# design.net
KiCad netlist of a schematic drawn in Altium Designer
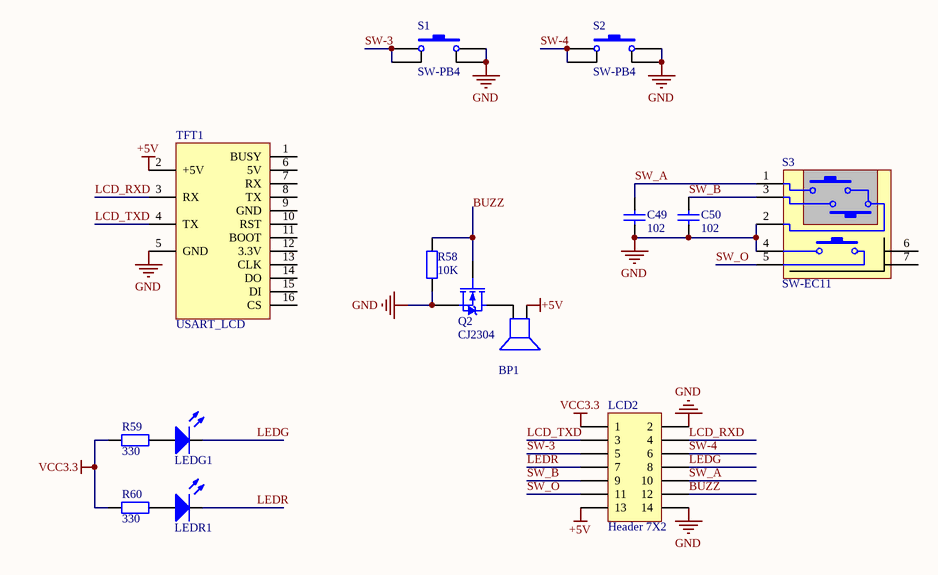
[diagram p0: 显示面板.SchDoc]

(export (version "E")
  (design (tool "Eeschema 10.0.6"))
  (components
    (comp (ref "BP1")
      (value "BUZZER")
      (footprint "蜂鸣器")
      (description "蜂鸣器")
      (libsource (lib "MY_Library") (part "BUZZER"))
    )
    (comp (ref "C49")
      (value "102")
      (footprint "C-RAD-0603")
      (description "无极性电容")
      (fields (field (name "Comment") "Cap") (field (name "PUBLISHER") "Altium Limited"))
      (libsource (lib "Fszhang") (part "Cap"))
    )
    (comp (ref "C50")
      (value "102")
      (footprint "C-RAD-0603")
      (description "无极性电容")
      (fields (field (name "Comment") "Cap") (field (name "PUBLISHER") "Altium Limited"))
      (libsource (lib "Fszhang") (part "Cap"))
    )
    (comp (ref "LCD2")
      (value "Header 7X2")
      (footprint "HDR7X2_A1")
      (description "Header, 7-Pin")
      (fields (field (name "PUBLISHER") "Altium Limited"))
      (libsource (lib "Fszhang") (part "Header 7X2"))
    )
    (comp (ref "LEDG1") (value "COLOUR") (footprint "LEDφ6") (libsource (lib "MY_Library") (part "ledφ6")))
    (comp (ref "LEDR1") (value "COLOUR") (footprint "LEDφ6") (libsource (lib "MY_Library") (part "ledφ6")))
    (comp (ref "Q2")
      (value "CJ2304")
      (footprint "SOT-23")
      (description "N-Channel MOSFET")
      (fields (field (name "PUBLISHER") "Altium Limited"))
      (libsource (lib "Fszhang") (part "MOSFET-N"))
    )
    (comp (ref "R58")
      (value "10K")
      (footprint "0603-1")
      (description "贴片电阻")
      (fields (field (name "Comment") "Res1") (field (name "PUBLISHER") "Altium Limited"))
      (libsource (lib "") (part "Res1_1"))
    )
    (comp (ref "R59")
      (value "330")
      (footprint "0603-1")
      (description "贴片电阻")
      (fields (field (name "Comment") "Res1") (field (name "PUBLISHER") "Altium Limited"))
      (libsource (lib "Fszhang") (part "Res1"))
    )
    (comp (ref "R60")
      (value "330")
      (footprint "0603-1")
      (description "贴片电阻")
      (fields (field (name "Comment") "Res1") (field (name "PUBLISHER") "Altium Limited"))
      (libsource (lib "Fszhang") (part "Res1"))
    )
    (comp (ref "S1")
      (value "SW-PB4")
      (footprint "SW_PB4_A1")
      (description "微动开关")
      (fields (field (name "PUBLISHER") "Altium Limited"))
      (libsource (lib "Fszhang") (part "SW-PB4"))
    )
    (comp (ref "S2")
      (value "SW-PB4")
      (footprint "SW_PB4_A1")
      (description "微动开关")
      (fields (field (name "PUBLISHER") "Altium Limited"))
      (libsource (lib "Fszhang") (part "SW-PB4"))
    )
    (comp (ref "S3")
      (value "SW-EC11")
      (footprint "EC11")
      (description "旋转编码开关")
      (fields (field (name "PUBLISHER") "Altium Limited"))
      (libsource (lib "Fszhang") (part "SW-EC11"))
    )
    (comp (ref "TFT1")
      (value "USART_LCD")
      (footprint "3.5寸")
      (description "usart串口屏")
      (libsource (lib "UASRT_LCD") (part "USART_LCD"))
    )
  )
  (nets
    (net (code "1") (name "+5V") (class "Default")
      (node (ref "BP1") (pin "1") (pinfunction "+_1") (pintype "passive"))
      (node (ref "LCD2") (pin "13") (pinfunction "13_13") (pintype "passive"))
      (node (ref "TFT1") (pin "2") (pinfunction "+5V_2") (pintype "passive"))
    )
    (net (code "2") (name "/BUZZ") (class "Default")
      (node (ref "LCD2") (pin "12") (pinfunction "12_12") (pintype "passive"))
      (node (ref "Q2") (pin "1") (pinfunction "G_1") (pintype "passive"))
      (node (ref "R58") (pin "2") (pinfunction "2_2") (pintype "passive"))
    )
    (net (code "3") (name "/LCD_RXD") (class "Default")
      (node (ref "LCD2") (pin "4") (pinfunction "4_4") (pintype "passive"))
      (node (ref "TFT1") (pin "3") (pinfunction "RX_3") (pintype "passive"))
    )
    (net (code "4") (name "/LCD_TXD") (class "Default")
      (node (ref "LCD2") (pin "3") (pinfunction "3_3") (pintype "passive"))
      (node (ref "TFT1") (pin "4") (pinfunction "TX_4") (pintype "passive"))
    )
    (net (code "5") (name "/LEDG") (class "Default")
      (node (ref "LCD2") (pin "8") (pinfunction "8_8") (pintype "passive"))
      (node (ref "LEDG1") (pin "2") (pinfunction "-_2") (pintype "passive"))
    )
    (net (code "6") (name "/LEDR") (class "Default")
      (node (ref "LCD2") (pin "7") (pinfunction "7_7") (pintype "passive"))
      (node (ref "LEDR1") (pin "2") (pinfunction "-_2") (pintype "passive"))
    )
    (net (code "7") (name "/SW-3") (class "Default")
      (node (ref "LCD2") (pin "5") (pinfunction "5_5") (pintype "passive"))
      (node (ref "S1") (pin "1") (pinfunction "1_1") (pintype "passive"))
      (node (ref "S1") (pin "4") (pinfunction "4_4") (pintype "passive"))
    )
    (net (code "8") (name "/SW-4") (class "Default")
      (node (ref "LCD2") (pin "6") (pinfunction "6_6") (pintype "passive"))
      (node (ref "S2") (pin "1") (pinfunction "1_1") (pintype "passive"))
      (node (ref "S2") (pin "4") (pinfunction "4_4") (pintype "passive"))
    )
    (net (code "9") (name "/SW_A") (class "Default")
      (node (ref "C49") (pin "2") (pinfunction "2_2") (pintype "passive"))
      (node (ref "LCD2") (pin "10") (pinfunction "10_10") (pintype "passive"))
      (node (ref "S3") (pin "1") (pinfunction "1_1") (pintype "passive"))
    )
    (net (code "10") (name "/SW_B") (class "Default")
      (node (ref "C50") (pin "2") (pinfunction "2_2") (pintype "passive"))
      (node (ref "LCD2") (pin "9") (pinfunction "9_9") (pintype "passive"))
      (node (ref "S3") (pin "3") (pinfunction "3_3") (pintype "passive"))
    )
    (net (code "11") (name "/SW_O") (class "Default")
      (node (ref "LCD2") (pin "11") (pinfunction "11_11") (pintype "passive"))
      (node (ref "S3") (pin "5") (pinfunction "5_5") (pintype "passive"))
    )
    (net (code "12") (name "GND") (class "Default")
      (node (ref "C49") (pin "1") (pinfunction "1_1") (pintype "passive"))
      (node (ref "C50") (pin "1") (pinfunction "1_1") (pintype "passive"))
      (node (ref "LCD2") (pin "14") (pinfunction "14_14") (pintype "passive"))
      (node (ref "LCD2") (pin "2") (pinfunction "2_2") (pintype "passive"))
      (node (ref "Q2") (pin "2") (pinfunction "S_2") (pintype "passive"))
      (node (ref "R58") (pin "1") (pinfunction "1_1") (pintype "passive"))
      (node (ref "S1") (pin "2") (pinfunction "2_2") (pintype "passive"))
      (node (ref "S1") (pin "3") (pinfunction "3_3") (pintype "passive"))
      (node (ref "S2") (pin "2") (pinfunction "2_2") (pintype "passive"))
      (node (ref "S2") (pin "3") (pinfunction "3_3") (pintype "passive"))
      (node (ref "S3") (pin "2") (pinfunction "2_2") (pintype "passive"))
      (node (ref "S3") (pin "4") (pinfunction "4_4") (pintype "passive"))
      (node (ref "TFT1") (pin "5") (pinfunction "GND_5") (pintype "passive"))
    )
    (net (code "13") (name "Net-(BP1--)") (class "Default")
      (node (ref "BP1") (pin "2") (pinfunction "-_2") (pintype "passive"))
      (node (ref "Q2") (pin "3") (pinfunction "D_3") (pintype "passive"))
    )
    (net (code "14") (name "Net-(LEDG1-+)") (class "Default")
      (node (ref "LEDG1") (pin "1") (pinfunction "+_1") (pintype "passive"))
      (node (ref "R59") (pin "1") (pinfunction "1_1") (pintype "passive"))
    )
    (net (code "15") (name "Net-(LEDR1-+)") (class "Default")
      (node (ref "LEDR1") (pin "1") (pinfunction "+_1") (pintype "passive"))
      (node (ref "R60") (pin "1") (pinfunction "1_1") (pintype "passive"))
    )
    (net (code "16") (name "VCC3.3") (class "Default")
      (node (ref "LCD2") (pin "1") (pinfunction "1_1") (pintype "passive"))
      (node (ref "R59") (pin "2") (pinfunction "2_2") (pintype "passive"))
      (node (ref "R60") (pin "2") (pinfunction "2_2") (pintype "passive"))
    )
    (net (code "17") (name "unconnected-(S3-Pad6)") (class "Default")
      (node (ref "S3") (pin "6") (pinfunction "6_6") (pintype "passive"))
    )
    (net (code "18") (name "unconnected-(S3-Pad7)") (class "Default")
      (node (ref "S3") (pin "7") (pinfunction "7_7") (pintype "passive"))
    )
    (net (code "19") (name "unconnected-(TFT1-3.3V-Pad12)") (class "Default")
      (node (ref "TFT1") (pin "12") (pinfunction "3.3V_12") (pintype "passive"))
    )
    (net (code "20") (name "unconnected-(TFT1-5V-Pad6)") (class "Default")
      (node (ref "TFT1") (pin "6") (pinfunction "5V_6") (pintype "passive"))
    )
    (net (code "21") (name "unconnected-(TFT1-BOOT-Pad11)") (class "Default")
      (node (ref "TFT1") (pin "11") (pinfunction "BOOT_11") (pintype "passive"))
    )
    (net (code "22") (name "unconnected-(TFT1-BUSY-Pad1)") (class "Default")
      (node (ref "TFT1") (pin "1") (pinfunction "BUSY_1") (pintype "passive"))
    )
    (net (code "23") (name "unconnected-(TFT1-CLK-Pad13)") (class "Default")
      (node (ref "TFT1") (pin "13") (pinfunction "CLK_13") (pintype "passive"))
    )
    (net (code "24") (name "unconnected-(TFT1-CS-Pad16)") (class "Default")
      (node (ref "TFT1") (pin "16") (pinfunction "CS_16") (pintype "passive"))
    )
    (net (code "25") (name "unconnected-(TFT1-DI-Pad15)") (class "Default")
      (node (ref "TFT1") (pin "15") (pinfunction "DI_15") (pintype "passive"))
    )
    (net (code "26") (name "unconnected-(TFT1-DO-Pad14)") (class "Default")
      (node (ref "TFT1") (pin "14") (pinfunction "DO_14") (pintype "passive"))
    )
    (net (code "27") (name "unconnected-(TFT1-GND-Pad9)") (class "Default")
      (node (ref "TFT1") (pin "9") (pinfunction "GND_9") (pintype "passive"))
    )
    (net (code "28") (name "unconnected-(TFT1-RST-Pad10)") (class "Default")
      (node (ref "TFT1") (pin "10") (pinfunction "RST_10") (pintype "passive"))
    )
    (net (code "29") (name "unconnected-(TFT1-RX-Pad7)") (class "Default")
      (node (ref "TFT1") (pin "7") (pinfunction "RX_7") (pintype "passive"))
    )
    (net (code "30") (name "unconnected-(TFT1-TX-Pad8)") (class "Default")
      (node (ref "TFT1") (pin "8") (pinfunction "TX_8") (pintype "passive"))
    )
  )
)
